# 12VDC_5VDC_XL4015.net
KiCad netlist of a schematic drawn in Altium Designer
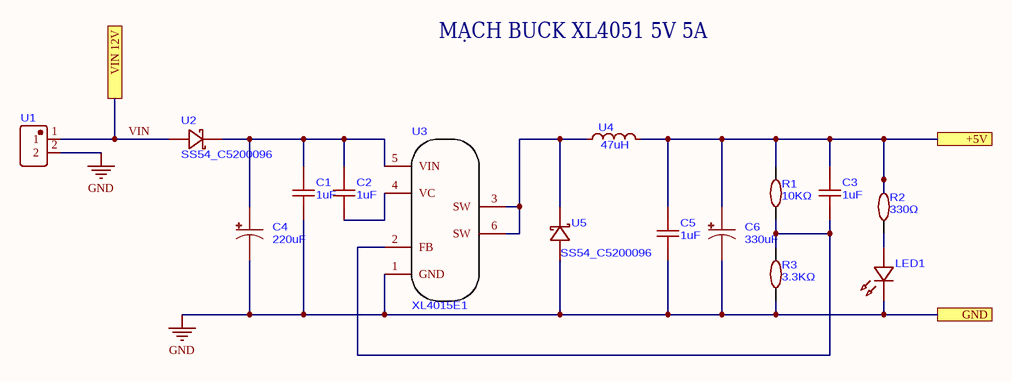
[diagram p0: 12VDC_5VDC_XL4015.SchDoc]

(export (version "E")
  (design (tool "Eeschema 10.0.6"))
  (components
    (comp (ref "C1")
      (value "1uF")
      (footprint "C0805")
      (libsource (lib "CAP 0.1uF") (part "CC0805KRX7R9BB104"))
    )
    (comp (ref "C2")
      (value "1uF")
      (footprint "C0805")
      (libsource (lib "CAP 0.1uF") (part "CC0805KRX7R9BB104"))
    )
    (comp (ref "C3")
      (value "1uF")
      (footprint "C0805")
      (libsource (lib "CAP 0.1uF") (part "CC0805KRX7R9BB104"))
    )
    (comp (ref "C4")
      (value "220uF")
      (footprint "CAP-SMD_BD10.0-L10.3-W10.3-LS11.0-R-RD")
      (libsource (lib "CAP +") (part "VEJ102M1ATR-1010"))
    )
    (comp (ref "C5")
      (value "1uF")
      (footprint "C0805")
      (libsource (lib "CAP 0.1uF") (part "CC0805KRX7R9BB104"))
    )
    (comp (ref "C6")
      (value "330uF")
      (footprint "CAP-SMD_BD10.0-L10.3-W10.3-LS11.0-R-RD")
      (libsource (lib "CAP +") (part "VEJ102M1ATR-1010"))
    )
    (comp (ref "LED1")
      (value "XL-2012SURC")
      (footprint "LED0805-RD_RED")
      (libsource (lib "LED_RED") (part "XL-2012SURC"))
    )
    (comp (ref "R1") (value "10KΩ") (footprint "R0805") (libsource (lib "RES 1K") (part "RC0805FR-071KL")))
    (comp (ref "R2") (value "330Ω") (footprint "R0805") (libsource (lib "RES 1K") (part "RC0805FR-071KL")))
    (comp (ref "R3") (value "3.3KΩ") (footprint "R0805") (libsource (lib "RES 1K") (part "RC0805FR-071KL")))
    (comp (ref "U1")
      (value "WJ500V-5.08-2P-13-00A")
      (footprint "CONN-TH_2P-P5.08-WJ500V-5.08-2P")
      (libsource (lib "header 3x2") (part "WJ500V-5.08-2P-13-00A"))
    )
    (comp (ref "U2")
      (value "SS54_C5200096")
      (footprint "SMB_L4.3-W3.6-LS5.4-RD")
      (libsource (lib "Diode SS34") (part "SS54_C5200096"))
    )
    (comp (ref "U3")
      (value "XL4015E1")
      (footprint "TO-263-5_L10.2-W8.9-P1.70-TL")
      (libsource (lib "LM2596") (part "XL4015E1"))
    )
    (comp (ref "U4")
      (value "47uH")
      (footprint "IND-TH_L14.0-W6.5-P8.00-D0.6")
      (libsource (lib "Inductor") (part "XR050125T680M-V"))
    )
    (comp (ref "U5")
      (value "SS54_C5200096")
      (footprint "SMB_L4.3-W3.6-LS5.4-RD")
      (libsource (lib "Diode SS34") (part "SS54_C5200096"))
    )
  )
  (nets
    (net (code "1") (name "/+5V") (class "Default")
      (node (ref "C3") (pin "2") (pinfunction "2_2") (pintype "passive"))
      (node (ref "C5") (pin "2") (pinfunction "2_2") (pintype "passive"))
      (node (ref "C6") (pin "1") (pinfunction "1_1") (pintype "passive"))
      (node (ref "R1") (pin "2") (pinfunction "2_2") (pintype "passive"))
      (node (ref "R2") (pin "2") (pinfunction "2_2") (pintype "passive"))
      (node (ref "U4") (pin "2") (pinfunction "2_2") (pintype "passive"))
    )
    (net (code "2") (name "/VIN") (class "Default")
      (node (ref "U1") (pin "1") (pinfunction "1_1") (pintype "passive"))
      (node (ref "U2") (pin "2") (pinfunction "2_2") (pintype "passive"))
    )
    (net (code "3") (name "GND") (class "Default")
      (node (ref "C1") (pin "1") (pinfunction "1_1") (pintype "passive"))
      (node (ref "C4") (pin "2") (pinfunction "2_2") (pintype "passive"))
      (node (ref "C5") (pin "1") (pinfunction "1_1") (pintype "passive"))
      (node (ref "C6") (pin "2") (pinfunction "2_2") (pintype "passive"))
      (node (ref "LED1") (pin "1") (pinfunction "K_1") (pintype "passive"))
      (node (ref "R3") (pin "1") (pinfunction "1_1") (pintype "passive"))
      (node (ref "U1") (pin "2") (pinfunction "2_2") (pintype "passive"))
      (node (ref "U3") (pin "1") (pinfunction "GND_1") (pintype "passive"))
      (node (ref "U5") (pin "2") (pinfunction "2_2") (pintype "passive"))
    )
    (net (code "4") (name "Net-(LED1-A)") (class "Default")
      (node (ref "LED1") (pin "2") (pinfunction "A_2") (pintype "passive"))
      (node (ref "R2") (pin "1") (pinfunction "1_1") (pintype "passive"))
    )
    (net (code "5") (name "Net-(U3-FB)") (class "Default")
      (node (ref "C3") (pin "1") (pinfunction "1_1") (pintype "passive"))
      (node (ref "R1") (pin "1") (pinfunction "1_1") (pintype "passive"))
      (node (ref "R3") (pin "2") (pinfunction "2_2") (pintype "passive"))
      (node (ref "U3") (pin "2") (pinfunction "FB_2") (pintype "passive"))
    )
    (net (code "6") (name "Net-(U3-SW-Pad3)") (class "Default")
      (node (ref "U3") (pin "3") (pinfunction "SW_3") (pintype "passive"))
      (node (ref "U3") (pin "6") (pinfunction "SW_6") (pintype "passive"))
      (node (ref "U4") (pin "1") (pinfunction "1_1") (pintype "passive"))
      (node (ref "U5") (pin "1") (pinfunction "1_1") (pintype "passive"))
    )
    (net (code "7") (name "Net-(U3-VC)") (class "Default")
      (node (ref "C2") (pin "1") (pinfunction "1_1") (pintype "passive"))
      (node (ref "U3") (pin "4") (pinfunction "VC_4") (pintype "passive"))
    )
    (net (code "8") (name "Net-(U3-VIN)") (class "Default")
      (node (ref "C1") (pin "2") (pinfunction "2_2") (pintype "passive"))
      (node (ref "C2") (pin "2") (pinfunction "2_2") (pintype "passive"))
      (node (ref "C4") (pin "1") (pinfunction "1_1") (pintype "passive"))
      (node (ref "U2") (pin "1") (pinfunction "1_1") (pintype "passive"))
      (node (ref "U3") (pin "5") (pinfunction "VIN_5") (pintype "passive"))
    )
  )
)
